# SCH_Gyver_LED_drill_2025-12-19.net
KiCad netlist of a schematic drawn in EasyEDA
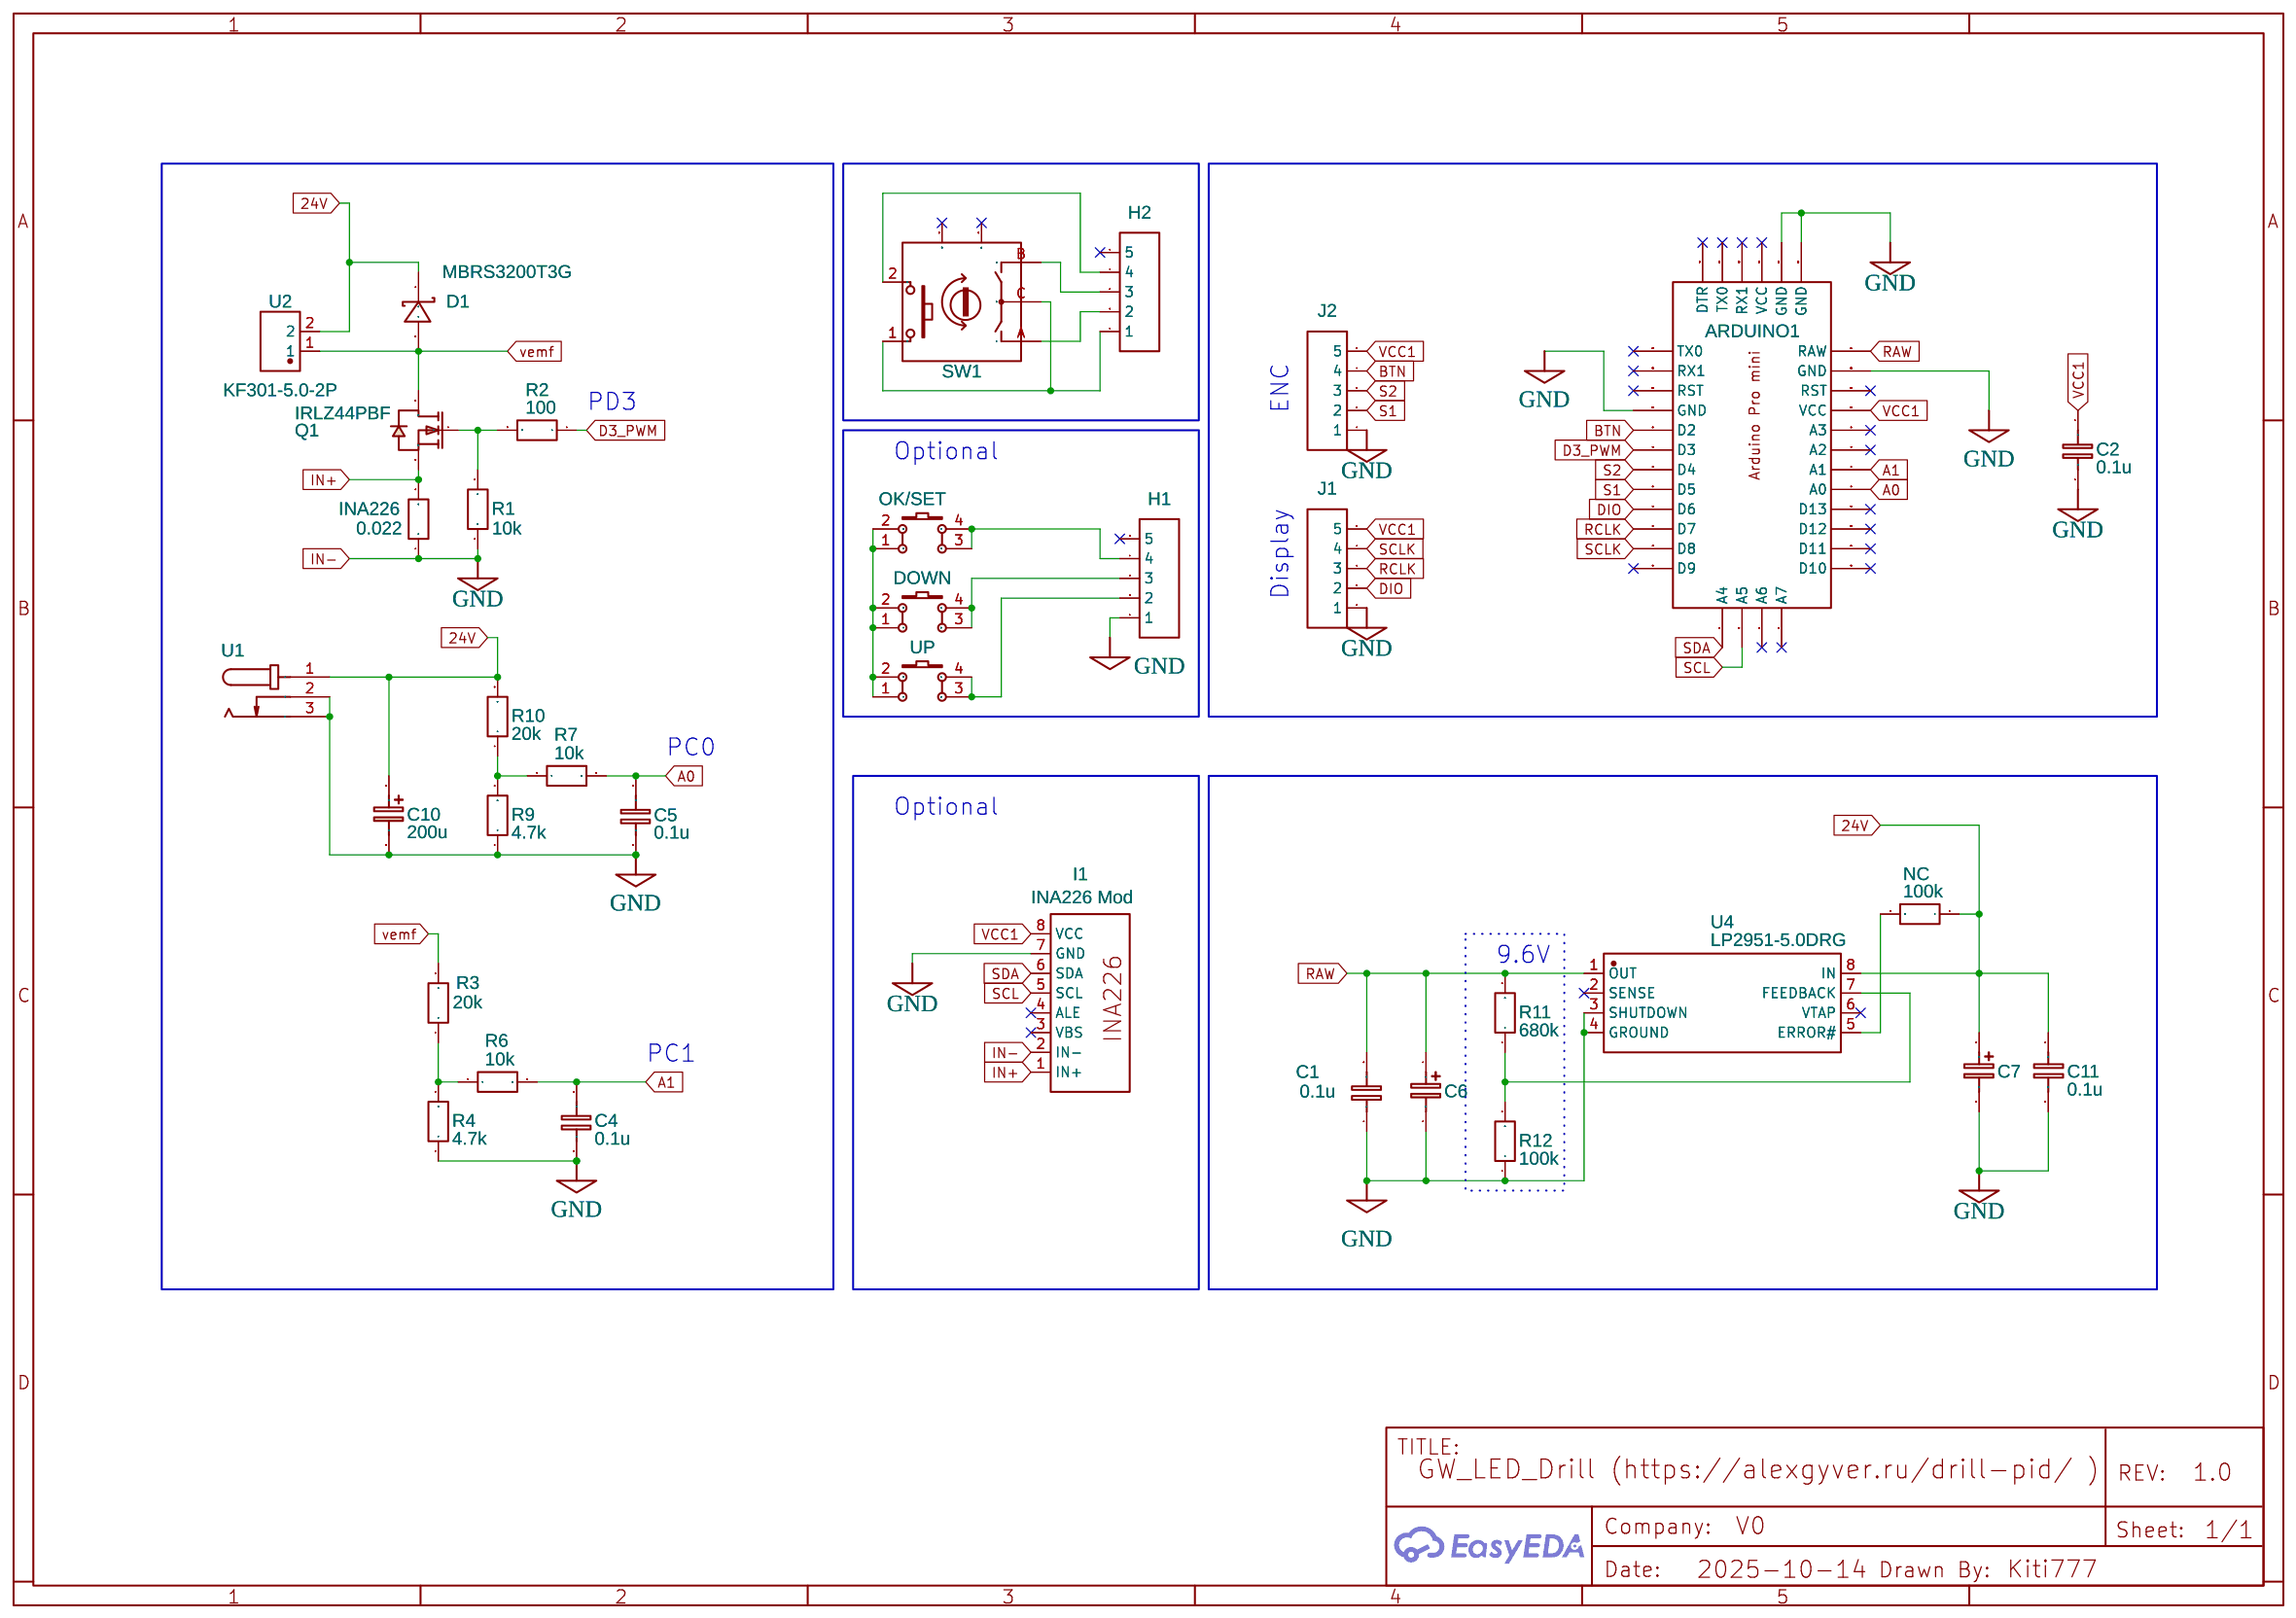
[diagram p0: Schematics]
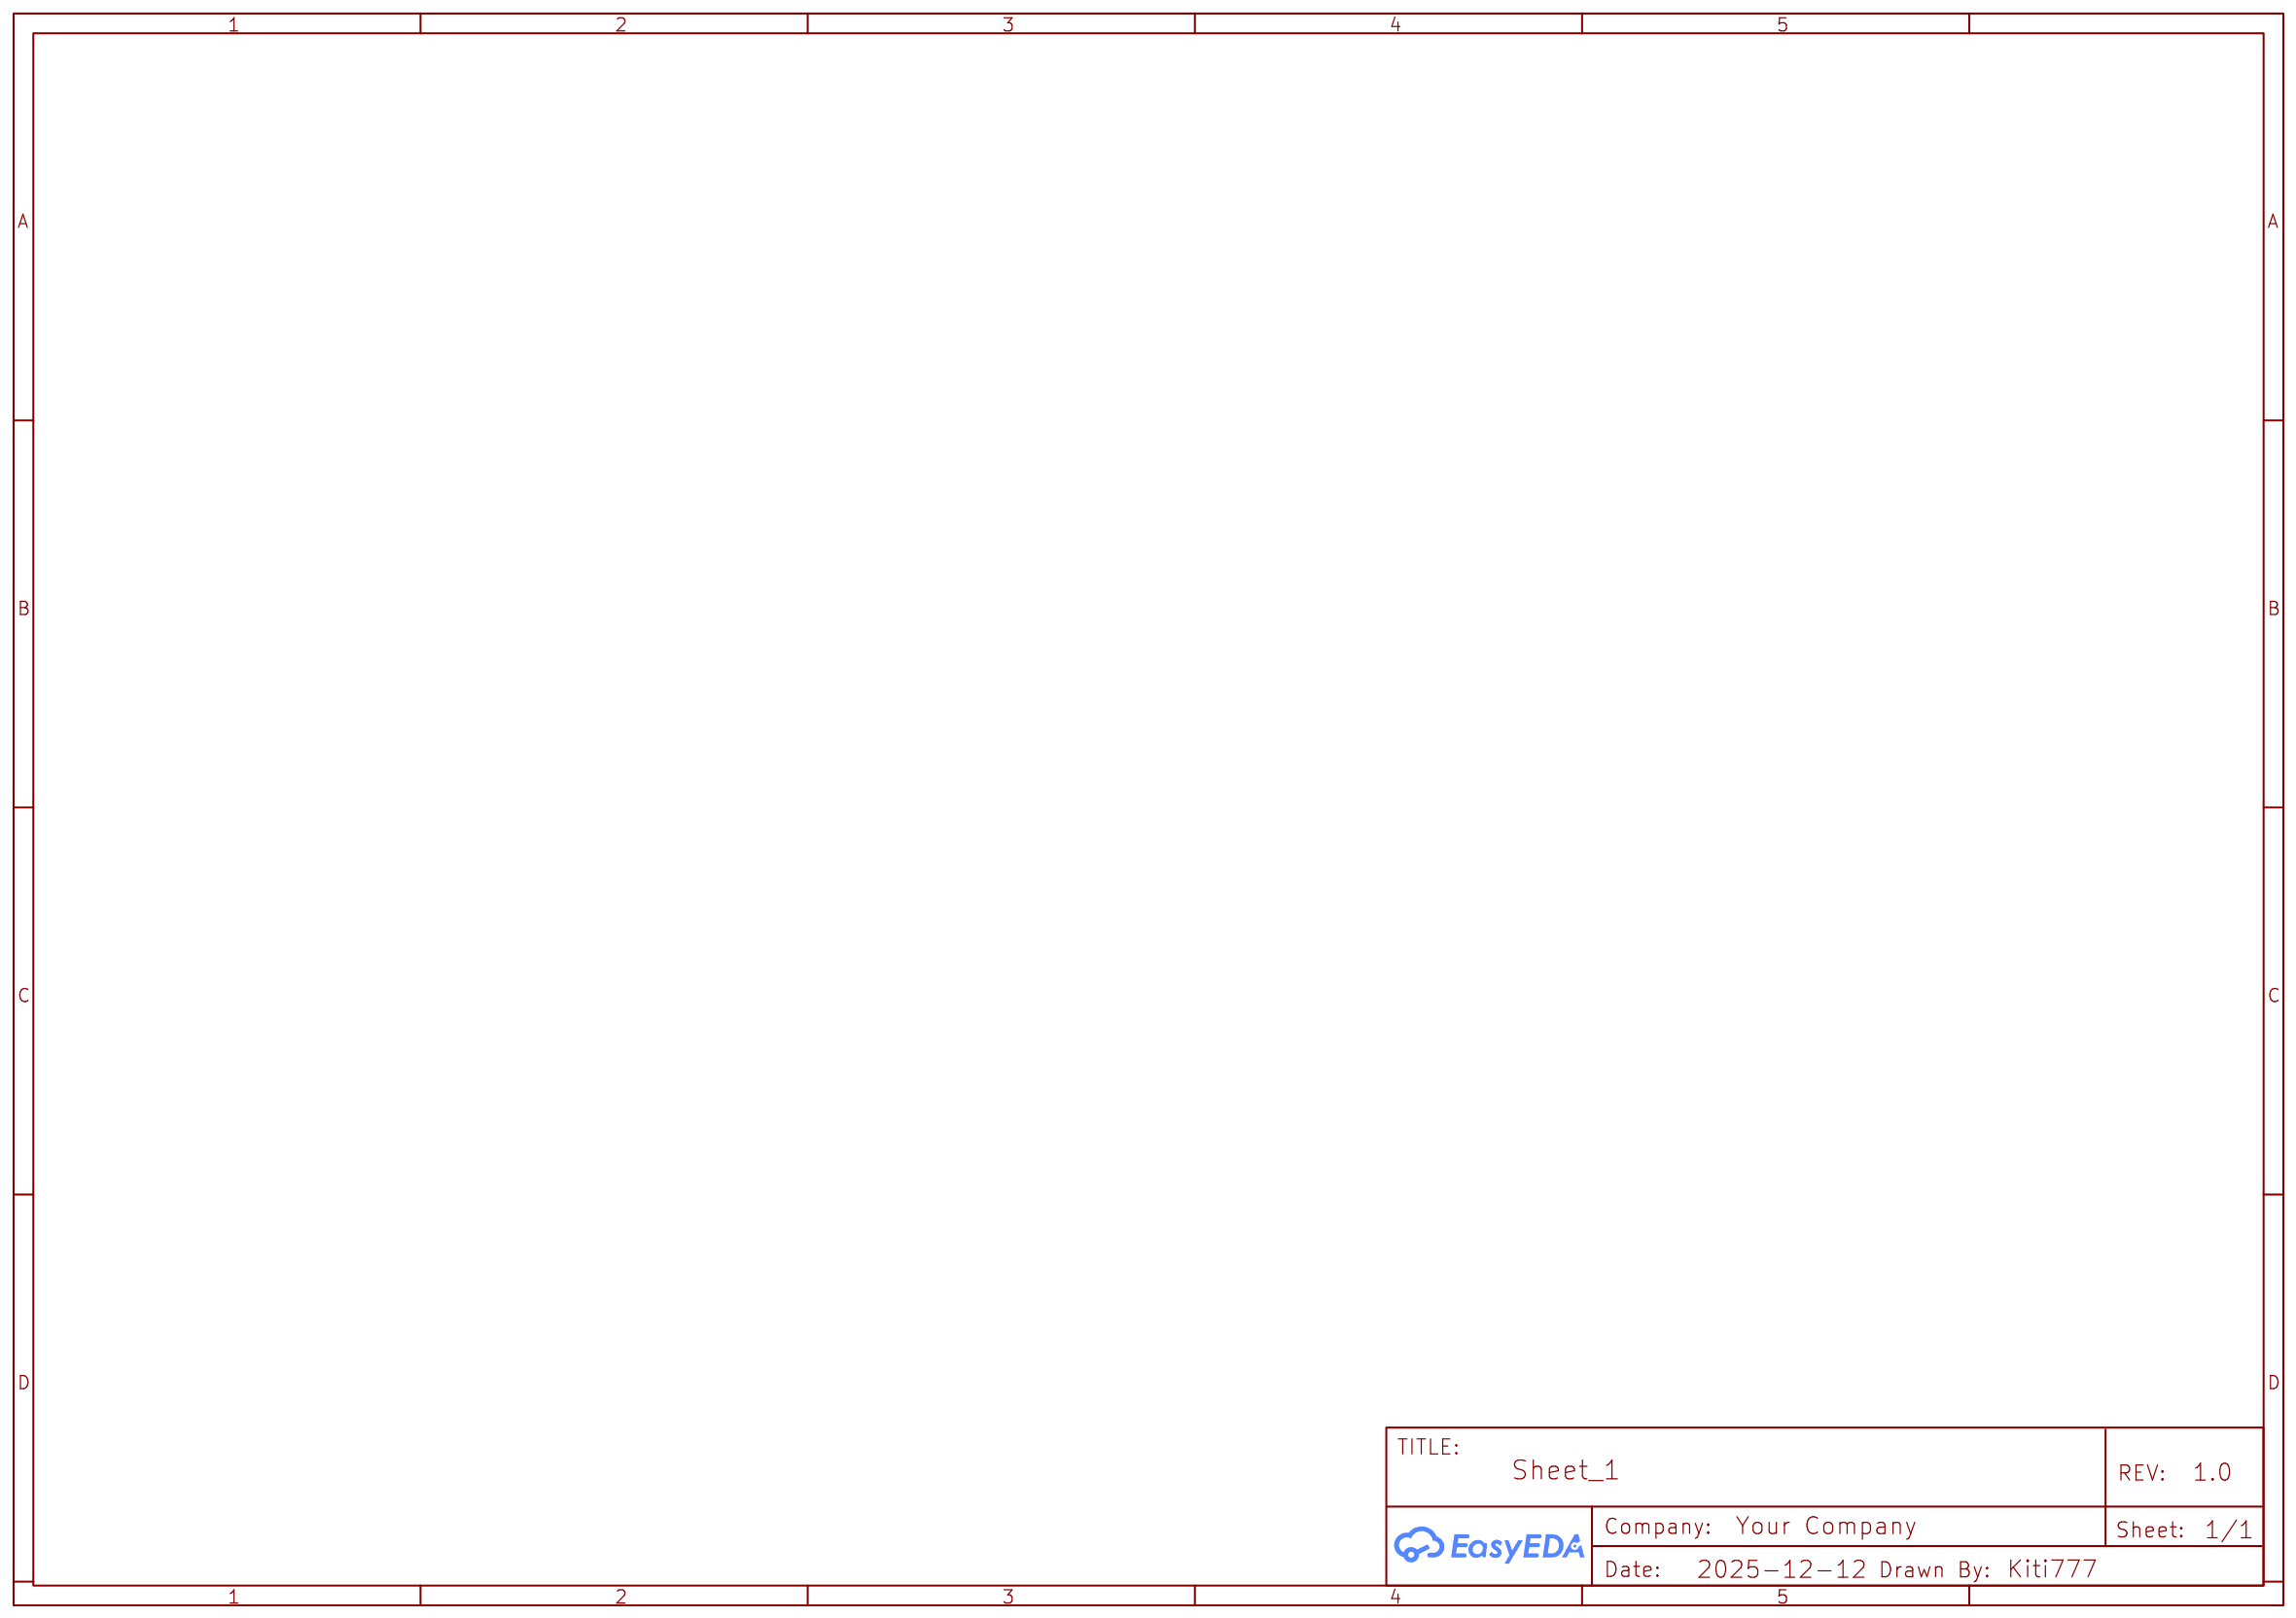
[diagram p1: INA226]

(export (version "E")
  (design (tool "Eeschema 10.0.6"))
  (components
    (comp (ref "ARDUINO1") (value "ARDUINO PRO MINI") (libsource (lib "") (part "ARDUINO PRO MINI")))
    (comp (ref "C1") (value "0.1u") (libsource (lib "") (part "C_1206_EU_2")))
    (comp (ref "C2") (value "0.1u") (libsource (lib "") (part "C_0805_EU")))
    (comp (ref "C4") (value "0.1u") (libsource (lib "") (part "C_0805_EU_1")))
    (comp (ref "C5") (value "0.1u") (libsource (lib "") (part "C_1206_EU_1")))
    (comp (ref "C6")
      (value "TANTALUM SMT CAPACITOR 330UF C")
      (fields (field (name "Manufacturer Part") "Tantalum SMT Capacitor 330uF C"))
      (libsource (lib "") (part "TANTALUM SMT CAPACITOR 330UF C"))
    )
    (comp (ref "C7")
      (value "TANTALUM SMT CAPACITOR 330UF C")
      (fields (field (name "Manufacturer Part") "Tantalum SMT Capacitor 330uF C"))
      (libsource (lib "") (part "TANTALUM SMT CAPACITOR 330UF C"))
    )
    (comp (ref "C10") (value "200u") (libsource (lib "") (part "CE_SMD_D8.0×H10.5_EU")))
    (comp (ref "C11") (value "0.1u") (libsource (lib "") (part "C_1206_EU")))
    (comp (ref "D1")
      (value "MBRS3200T3G")
      (fields (field (name "Manufacturer") "onsemi(安森美)"))
      (libsource (lib "") (part "MBRS3200T3G"))
    )
    (comp (ref "DOWN")
      (value "K4-6×6_TH")
      (fields (field (name "Manufacturer Part") "K2-1102DP-E4SW-04") (field (name "Manufacturer") "韩国韩荣"))
      (libsource (lib "") (part "K4-6×6_TH_2"))
    )
    (comp (ref "H1") (value "HDR-F-2.54_1x5") (libsource (lib "") (part "HDR-F-2.54_1x5")))
    (comp (ref "H2") (value "HDR-F-2.54_1x5") (libsource (lib "") (part "HDR-F-2.54_1x5")))
    (comp (ref "I1") (value "INA226 Mod") (libsource (lib "") (part "INA226_1 Modulo")))
    (comp (ref "INA226") (value "0.022") (libsource (lib "") (part "R_2010_EU")))
    (comp (ref "J1") (value "HDR-M-2.54_1x5") (libsource (lib "") (part "HDR-M-2.54_1x5")))
    (comp (ref "J2") (value "HDR-M-2.54_1x5") (libsource (lib "") (part "HDR-M-2.54_1x5")))
    (comp (ref "NC") (value "100k") (libsource (lib "") (part "R_0805_EU_1")))
    (comp (ref "OK/SET")
      (value "K4-6×6_TH")
      (fields (field (name "Manufacturer Part") "K2-1102DP-E4SW-04") (field (name "Manufacturer") "韩国韩荣"))
      (libsource (lib "") (part "K4-6×6_TH"))
    )
    (comp (ref "Q1")
      (value "IRLZ44PBF")
      (fields (field (name "Manufacturer Part") "IRLZ44PBF-VB") (field (name "Manufacturer") "VBsemi(微碧半导体)"))
      (libsource (lib "") (part "IRLZ44PBF"))
    )
    (comp (ref "R1") (value "10k") (libsource (lib "") (part "R_1206_EU")))
    (comp (ref "R2") (value "100") (libsource (lib "") (part "R_1206_EU_1")))
    (comp (ref "R3") (value "20k") (libsource (lib "") (part "R_1206_EU")))
    (comp (ref "R4") (value "4.7k") (libsource (lib "") (part "R_1206_EU")))
    (comp (ref "R6") (value "10k") (libsource (lib "") (part "R_1206_EU_2")))
    (comp (ref "R7") (value "10k") (libsource (lib "") (part "R_1206_EU_2")))
    (comp (ref "R9") (value "4.7k") (libsource (lib "") (part "R_1206_EU")))
    (comp (ref "R10") (value "20k") (libsource (lib "") (part "R_1206_EU")))
    (comp (ref "R11") (value "680k") (libsource (lib "") (part "R_0805_EU")))
    (comp (ref "R12") (value "100k") (libsource (lib "") (part "R_0805_EU")))
    (comp (ref "SW1")
      (value "PEC11R-4015F-S0024")
      (fields (field (name "Manufacturer") "BOURNS"))
      (libsource (lib "") (part "PEC11R-4015F-S0024"))
    )
    (comp (ref "U1")
      (value "ZX-DC-WC26.4")
      (fields (field (name "Manufacturer") "Megastar(兆星)"))
      (libsource (lib "") (part "ZX-DC-WC26.4"))
    )
    (comp (ref "U2")
      (value "KF301-5.0-2P")
      (fields (field (name "Manufacturer") "KEFA(科发)"))
      (libsource (lib "") (part "KF301-5.0-2P"))
    )
    (comp (ref "U4")
      (value "LP2951-5.0DRG")
      (fields (field (name "Manufacturer") "HGC(深圳汉芯)"))
      (libsource (lib "") (part "LP2951-5.0DRG"))
    )
    (comp (ref "UP")
      (value "K4-6×6_TH")
      (fields (field (name "Manufacturer Part") "K2-1102DP-E4SW-04") (field (name "Manufacturer") "韩国韩荣"))
      (libsource (lib "") (part "K4-6×6_TH_1"))
    )
  )
  (nets
    (net (code "1") (name "24V") (class "Default")
      (node (ref "C10") (pin "1") (pinfunction "1_1") (pintype "unspecified"))
      (node (ref "C11") (pin "1") (pinfunction "1_1") (pintype "unspecified"))
      (node (ref "C7") (pin "1") (pinfunction "1_1") (pintype "unspecified"))
      (node (ref "D1") (pin "1") (pinfunction "C_1") (pintype "unspecified"))
      (node (ref "NC") (pin "1") (pinfunction "1_1") (pintype "unspecified"))
      (node (ref "R10") (pin "2") (pinfunction "2_2") (pintype "unspecified"))
      (node (ref "U1") (pin "1") (pinfunction "1_1") (pintype "unspecified"))
      (node (ref "U2") (pin "2") (pinfunction "2_2") (pintype "unspecified"))
      (node (ref "U4") (pin "8") (pinfunction "IN_8") (pintype "unspecified"))
    )
    (net (code "2") (name "A0") (class "Default")
      (node (ref "ARDUINO1") (pin "A0") (pinfunction "A0_A0") (pintype "bidirectional"))
      (node (ref "C5") (pin "2") (pinfunction "2_2") (pintype "unspecified"))
      (node (ref "R7") (pin "2") (pinfunction "2_2") (pintype "unspecified"))
    )
    (net (code "3") (name "A1") (class "Default")
      (node (ref "ARDUINO1") (pin "A1") (pinfunction "A1_A1") (pintype "bidirectional"))
      (node (ref "C4") (pin "2") (pinfunction "2_2") (pintype "unspecified"))
      (node (ref "R6") (pin "2") (pinfunction "2_2") (pintype "unspecified"))
    )
    (net (code "4") (name "BTN") (class "Default")
      (node (ref "ARDUINO1") (pin "D2") (pinfunction "D2_D2") (pintype "bidirectional"))
      (node (ref "J2") (pin "4") (pinfunction "4_4") (pintype "unspecified"))
    )
    (net (code "5") (name "D3_PWM") (class "Default")
      (node (ref "ARDUINO1") (pin "D3") (pinfunction "D3_D3") (pintype "bidirectional"))
      (node (ref "R2") (pin "1") (pinfunction "1_1") (pintype "unspecified"))
    )
    (net (code "6") (name "DIO") (class "Default")
      (node (ref "ARDUINO1") (pin "D6") (pinfunction "D6_D6") (pintype "bidirectional"))
      (node (ref "J1") (pin "2") (pinfunction "2_2") (pintype "unspecified"))
    )
    (net (code "7") (name "IN+") (class "Default")
      (node (ref "I1") (pin "1") (pinfunction "IN+_1") (pintype "unspecified"))
      (node (ref "INA226") (pin "2") (pinfunction "2_2") (pintype "unspecified"))
      (node (ref "Q1") (pin "3") (pinfunction "S_3") (pintype "unspecified"))
    )
    (net (code "8") (name "IN-") (class "Default")
      (node (ref "ARDUINO1") (pin "GND@0") (pinfunction "GND_GND@0") (pintype "bidirectional"))
      (node (ref "ARDUINO1") (pin "GND@1") (pinfunction "GND_GND@1") (pintype "bidirectional"))
      (node (ref "ARDUINO1") (pin "GND@2") (pinfunction "GND_GND@2") (pintype "bidirectional"))
      (node (ref "ARDUINO1") (pin "GND@3") (pinfunction "GND_GND@3") (pintype "bidirectional"))
      (node (ref "C1") (pin "1") (pinfunction "1_1") (pintype "unspecified"))
      (node (ref "C10") (pin "2") (pinfunction "2_2") (pintype "unspecified"))
      (node (ref "C11") (pin "2") (pinfunction "2_2") (pintype "unspecified"))
      (node (ref "C2") (pin "1") (pinfunction "1_1") (pintype "unspecified"))
      (node (ref "C4") (pin "1") (pinfunction "1_1") (pintype "unspecified"))
      (node (ref "C5") (pin "1") (pinfunction "1_1") (pintype "unspecified"))
      (node (ref "C6") (pin "2") (pinfunction "2_2") (pintype "unspecified"))
      (node (ref "C7") (pin "2") (pinfunction "2_2") (pintype "unspecified"))
      (node (ref "H1") (pin "1") (pinfunction "1_1") (pintype "unspecified"))
      (node (ref "I1") (pin "2") (pinfunction "IN-_2") (pintype "unspecified"))
      (node (ref "I1") (pin "7") (pinfunction "GND_7") (pintype "unspecified"))
      (node (ref "INA226") (pin "1") (pinfunction "1_1") (pintype "unspecified"))
      (node (ref "J1") (pin "1") (pinfunction "1_1") (pintype "unspecified"))
      (node (ref "J2") (pin "1") (pinfunction "1_1") (pintype "unspecified"))
      (node (ref "R1") (pin "1") (pinfunction "1_1") (pintype "unspecified"))
      (node (ref "R12") (pin "1") (pinfunction "1_1") (pintype "unspecified"))
      (node (ref "R4") (pin "1") (pinfunction "1_1") (pintype "unspecified"))
      (node (ref "R9") (pin "1") (pinfunction "1_1") (pintype "unspecified"))
      (node (ref "U1") (pin "2") (pinfunction "2_2") (pintype "unspecified"))
      (node (ref "U1") (pin "3") (pinfunction "3_3") (pintype "unspecified"))
      (node (ref "U4") (pin "3") (pinfunction "SHUTDOWN_3") (pintype "unspecified"))
      (node (ref "U4") (pin "4") (pinfunction "GROUND_4") (pintype "unspecified"))
    )
    (net (code "9") (name "Net-(DOWN-Pad1)") (class "Default")
      (node (ref "DOWN") (pin "1") (pinfunction "1_1") (pintype "unspecified"))
      (node (ref "DOWN") (pin "2") (pinfunction "2_2") (pintype "unspecified"))
      (node (ref "OK/SET") (pin "1") (pinfunction "1_1") (pintype "unspecified"))
      (node (ref "OK/SET") (pin "2") (pinfunction "2_2") (pintype "unspecified"))
      (node (ref "UP") (pin "1") (pinfunction "1_1") (pintype "unspecified"))
      (node (ref "UP") (pin "2") (pinfunction "2_2") (pintype "unspecified"))
    )
    (net (code "10") (name "Net-(DOWN-Pad3)") (class "Default")
      (node (ref "DOWN") (pin "3") (pinfunction "3_3") (pintype "unspecified"))
      (node (ref "DOWN") (pin "4") (pinfunction "4_4") (pintype "unspecified"))
      (node (ref "H1") (pin "3") (pinfunction "3_3") (pintype "unspecified"))
    )
    (net (code "11") (name "Net-(H1-Pad2)") (class "Default")
      (node (ref "H1") (pin "2") (pinfunction "2_2") (pintype "unspecified"))
      (node (ref "UP") (pin "3") (pinfunction "3_3") (pintype "unspecified"))
      (node (ref "UP") (pin "4") (pinfunction "4_4") (pintype "unspecified"))
    )
    (net (code "12") (name "Net-(H1-Pad4)") (class "Default")
      (node (ref "H1") (pin "4") (pinfunction "4_4") (pintype "unspecified"))
      (node (ref "OK/SET") (pin "3") (pinfunction "3_3") (pintype "unspecified"))
      (node (ref "OK/SET") (pin "4") (pinfunction "4_4") (pintype "unspecified"))
    )
    (net (code "13") (name "Net-(H2-Pad1)") (class "Default")
      (node (ref "H2") (pin "1") (pinfunction "1_1") (pintype "unspecified"))
      (node (ref "SW1") (pin "1") (pinfunction "1_1") (pintype "unspecified"))
      (node (ref "SW1") (pin "C") (pinfunction "C_C") (pintype "unspecified"))
    )
    (net (code "14") (name "Net-(H2-Pad2)") (class "Default")
      (node (ref "H2") (pin "2") (pinfunction "2_2") (pintype "unspecified"))
      (node (ref "SW1") (pin "A") (pinfunction "A_A") (pintype "unspecified"))
    )
    (net (code "15") (name "Net-(H2-Pad3)") (class "Default")
      (node (ref "H2") (pin "3") (pinfunction "3_3") (pintype "unspecified"))
      (node (ref "SW1") (pin "B") (pinfunction "B_B") (pintype "unspecified"))
    )
    (net (code "16") (name "Net-(H2-Pad4)") (class "Default")
      (node (ref "H2") (pin "4") (pinfunction "4_4") (pintype "unspecified"))
      (node (ref "SW1") (pin "2") (pinfunction "2_2") (pintype "unspecified"))
    )
    (net (code "17") (name "Net-(Q1-G)") (class "Default")
      (node (ref "Q1") (pin "1") (pinfunction "G_1") (pintype "unspecified"))
      (node (ref "R1") (pin "2") (pinfunction "2_2") (pintype "unspecified"))
      (node (ref "R2") (pin "2") (pinfunction "2_2") (pintype "unspecified"))
    )
    (net (code "18") (name "Net-(R3-Pad1)") (class "Default")
      (node (ref "R3") (pin "1") (pinfunction "1_1") (pintype "unspecified"))
      (node (ref "R4") (pin "2") (pinfunction "2_2") (pintype "unspecified"))
      (node (ref "R6") (pin "1") (pinfunction "1_1") (pintype "unspecified"))
    )
    (net (code "19") (name "Net-(R10-Pad1)") (class "Default")
      (node (ref "R10") (pin "1") (pinfunction "1_1") (pintype "unspecified"))
      (node (ref "R7") (pin "1") (pinfunction "1_1") (pintype "unspecified"))
      (node (ref "R9") (pin "2") (pinfunction "2_2") (pintype "unspecified"))
    )
    (net (code "20") (name "Net-(U4-ERROR#)") (class "Default")
      (node (ref "NC") (pin "2") (pinfunction "2_2") (pintype "unspecified"))
      (node (ref "U4") (pin "5") (pinfunction "ERROR#_5") (pintype "unspecified"))
    )
    (net (code "21") (name "Net-(U4-FEEDBACK)") (class "Default")
      (node (ref "R11") (pin "1") (pinfunction "1_1") (pintype "unspecified"))
      (node (ref "R12") (pin "2") (pinfunction "2_2") (pintype "unspecified"))
      (node (ref "U4") (pin "7") (pinfunction "FEEDBACK_7") (pintype "unspecified"))
    )
    (net (code "22") (name "RAW") (class "Default")
      (node (ref "ARDUINO1") (pin "RAW") (pinfunction "RAW_RAW") (pintype "bidirectional"))
      (node (ref "C1") (pin "2") (pinfunction "2_2") (pintype "unspecified"))
      (node (ref "C6") (pin "1") (pinfunction "1_1") (pintype "unspecified"))
      (node (ref "R11") (pin "2") (pinfunction "2_2") (pintype "unspecified"))
      (node (ref "U4") (pin "1") (pinfunction "OUT_1") (pintype "unspecified"))
    )
    (net (code "23") (name "RCLK") (class "Default")
      (node (ref "ARDUINO1") (pin "D7") (pinfunction "D7_D7") (pintype "bidirectional"))
      (node (ref "J1") (pin "3") (pinfunction "3_3") (pintype "unspecified"))
    )
    (net (code "24") (name "S1") (class "Default")
      (node (ref "ARDUINO1") (pin "D5") (pinfunction "D5_D5") (pintype "bidirectional"))
      (node (ref "J2") (pin "2") (pinfunction "2_2") (pintype "unspecified"))
    )
    (net (code "25") (name "S2") (class "Default")
      (node (ref "ARDUINO1") (pin "D4") (pinfunction "D4_D4") (pintype "bidirectional"))
      (node (ref "J2") (pin "3") (pinfunction "3_3") (pintype "unspecified"))
    )
    (net (code "26") (name "SCL") (class "Default")
      (node (ref "ARDUINO1") (pin "A5") (pinfunction "A5_A5") (pintype "bidirectional"))
      (node (ref "I1") (pin "5") (pinfunction "SCL_5") (pintype "unspecified"))
    )
    (net (code "27") (name "SCLK") (class "Default")
      (node (ref "ARDUINO1") (pin "D8") (pinfunction "D8_D8") (pintype "bidirectional"))
      (node (ref "J1") (pin "4") (pinfunction "4_4") (pintype "unspecified"))
    )
    (net (code "28") (name "SDA") (class "Default")
      (node (ref "ARDUINO1") (pin "A4") (pinfunction "A4_A4") (pintype "bidirectional"))
      (node (ref "I1") (pin "6") (pinfunction "SDA_6") (pintype "unspecified"))
    )
    (net (code "29") (name "VCC1") (class "Default")
      (node (ref "ARDUINO1") (pin "VCC@1") (pinfunction "VCC_VCC@1") (pintype "bidirectional"))
      (node (ref "C2") (pin "2") (pinfunction "2_2") (pintype "unspecified"))
      (node (ref "I1") (pin "8") (pinfunction "VCC_8") (pintype "unspecified"))
      (node (ref "J1") (pin "5") (pinfunction "5_5") (pintype "unspecified"))
      (node (ref "J2") (pin "5") (pinfunction "5_5") (pintype "unspecified"))
    )
    (net (code "30") (name "unconnected-(ARDUINO1-PadA2)") (class "Default")
      (node (ref "ARDUINO1") (pin "A2") (pinfunction "A2_A2") (pintype "bidirectional+no_connect"))
    )
    (net (code "31") (name "unconnected-(ARDUINO1-PadA3)") (class "Default")
      (node (ref "ARDUINO1") (pin "A3") (pinfunction "A3_A3") (pintype "bidirectional+no_connect"))
    )
    (net (code "32") (name "unconnected-(ARDUINO1-PadA6)") (class "Default")
      (node (ref "ARDUINO1") (pin "A6") (pinfunction "A6_A6") (pintype "bidirectional+no_connect"))
    )
    (net (code "33") (name "unconnected-(ARDUINO1-PadA7)") (class "Default")
      (node (ref "ARDUINO1") (pin "A7") (pinfunction "A7_A7") (pintype "bidirectional+no_connect"))
    )
    (net (code "34") (name "unconnected-(ARDUINO1-PadD9)") (class "Default")
      (node (ref "ARDUINO1") (pin "D9") (pinfunction "D9_D9") (pintype "bidirectional+no_connect"))
    )
    (net (code "35") (name "unconnected-(ARDUINO1-PadD10)") (class "Default")
      (node (ref "ARDUINO1") (pin "D10") (pinfunction "D10_D10") (pintype "bidirectional+no_connect"))
    )
    (net (code "36") (name "unconnected-(ARDUINO1-PadD11)") (class "Default")
      (node (ref "ARDUINO1") (pin "D11") (pinfunction "D11_D11") (pintype "bidirectional+no_connect"))
    )
    (net (code "37") (name "unconnected-(ARDUINO1-PadD12)") (class "Default")
      (node (ref "ARDUINO1") (pin "D12") (pinfunction "D12_D12") (pintype "bidirectional+no_connect"))
    )
    (net (code "38") (name "unconnected-(ARDUINO1-PadD13)") (class "Default")
      (node (ref "ARDUINO1") (pin "D13") (pinfunction "D13_D13") (pintype "bidirectional+no_connect"))
    )
    (net (code "39") (name "unconnected-(ARDUINO1-PadDTR)") (class "Default")
      (node (ref "ARDUINO1") (pin "DTR") (pinfunction "DTR_DTR") (pintype "bidirectional+no_connect"))
    )
    (net (code "40") (name "unconnected-(ARDUINO1-RST-PadRST@0)") (class "Default")
      (node (ref "ARDUINO1") (pin "RST@0") (pinfunction "RST_RST@0") (pintype "bidirectional+no_connect"))
    )
    (net (code "41") (name "unconnected-(ARDUINO1-RST-PadRST@1)") (class "Default")
      (node (ref "ARDUINO1") (pin "RST@1") (pinfunction "RST_RST@1") (pintype "bidirectional+no_connect"))
    )
    (net (code "42") (name "unconnected-(ARDUINO1-RX1-PadRX1@0)") (class "Default")
      (node (ref "ARDUINO1") (pin "RX1@0") (pinfunction "RX1_RX1@0") (pintype "bidirectional+no_connect"))
    )
    (net (code "43") (name "unconnected-(ARDUINO1-RX1-PadRX1@1)") (class "Default")
      (node (ref "ARDUINO1") (pin "RX1@1") (pinfunction "RX1_RX1@1") (pintype "bidirectional+no_connect"))
    )
    (net (code "44") (name "unconnected-(ARDUINO1-TX0-PadTX0@0)") (class "Default")
      (node (ref "ARDUINO1") (pin "TX0@0") (pinfunction "TX0_TX0@0") (pintype "bidirectional+no_connect"))
    )
    (net (code "45") (name "unconnected-(ARDUINO1-TX0-PadTX0@1)") (class "Default")
      (node (ref "ARDUINO1") (pin "TX0@1") (pinfunction "TX0_TX0@1") (pintype "bidirectional+no_connect"))
    )
    (net (code "46") (name "unconnected-(ARDUINO1-VCC-PadVCC@0)") (class "Default")
      (node (ref "ARDUINO1") (pin "VCC@0") (pinfunction "VCC_VCC@0") (pintype "bidirectional+no_connect"))
    )
    (net (code "47") (name "unconnected-(H1-Pad5)") (class "Default")
      (node (ref "H1") (pin "5") (pinfunction "5_5") (pintype "unspecified+no_connect"))
    )
    (net (code "48") (name "unconnected-(H2-Pad5)") (class "Default")
      (node (ref "H2") (pin "5") (pinfunction "5_5") (pintype "unspecified+no_connect"))
    )
    (net (code "49") (name "unconnected-(I1-ALE-Pad4)") (class "Default")
      (node (ref "I1") (pin "4") (pinfunction "ALE_4") (pintype "unspecified+no_connect"))
    )
    (net (code "50") (name "unconnected-(I1-VBS-Pad3)") (class "Default")
      (node (ref "I1") (pin "3") (pinfunction "VBS_3") (pintype "unspecified+no_connect"))
    )
    (net (code "51") (name "unconnected-(SW1-PadMT1)") (class "Default")
      (node (ref "SW1") (pin "MT1") (pinfunction "MT1_MT1") (pintype "unspecified+no_connect"))
    )
    (net (code "52") (name "unconnected-(SW1-PadMT2)") (class "Default")
      (node (ref "SW1") (pin "MT2") (pinfunction "MT2_MT2") (pintype "unspecified+no_connect"))
    )
    (net (code "53") (name "unconnected-(U4-SENSE-Pad2)") (class "Default")
      (node (ref "U4") (pin "2") (pinfunction "SENSE_2") (pintype "unspecified+no_connect"))
    )
    (net (code "54") (name "unconnected-(U4-VTAP-Pad6)") (class "Default")
      (node (ref "U4") (pin "6") (pinfunction "VTAP_6") (pintype "unspecified+no_connect"))
    )
    (net (code "55") (name "vemf") (class "Default")
      (node (ref "D1") (pin "2") (pinfunction "A_2") (pintype "unspecified"))
      (node (ref "Q1") (pin "2") (pinfunction "D_2") (pintype "unspecified"))
      (node (ref "R3") (pin "2") (pinfunction "2_2") (pintype "unspecified"))
      (node (ref "U2") (pin "1") (pinfunction "1_1") (pintype "unspecified"))
    )
  )
)
